# FIT_TCM_SN65LVDT100.net
KiCad netlist of a schematic drawn in Altium Designer
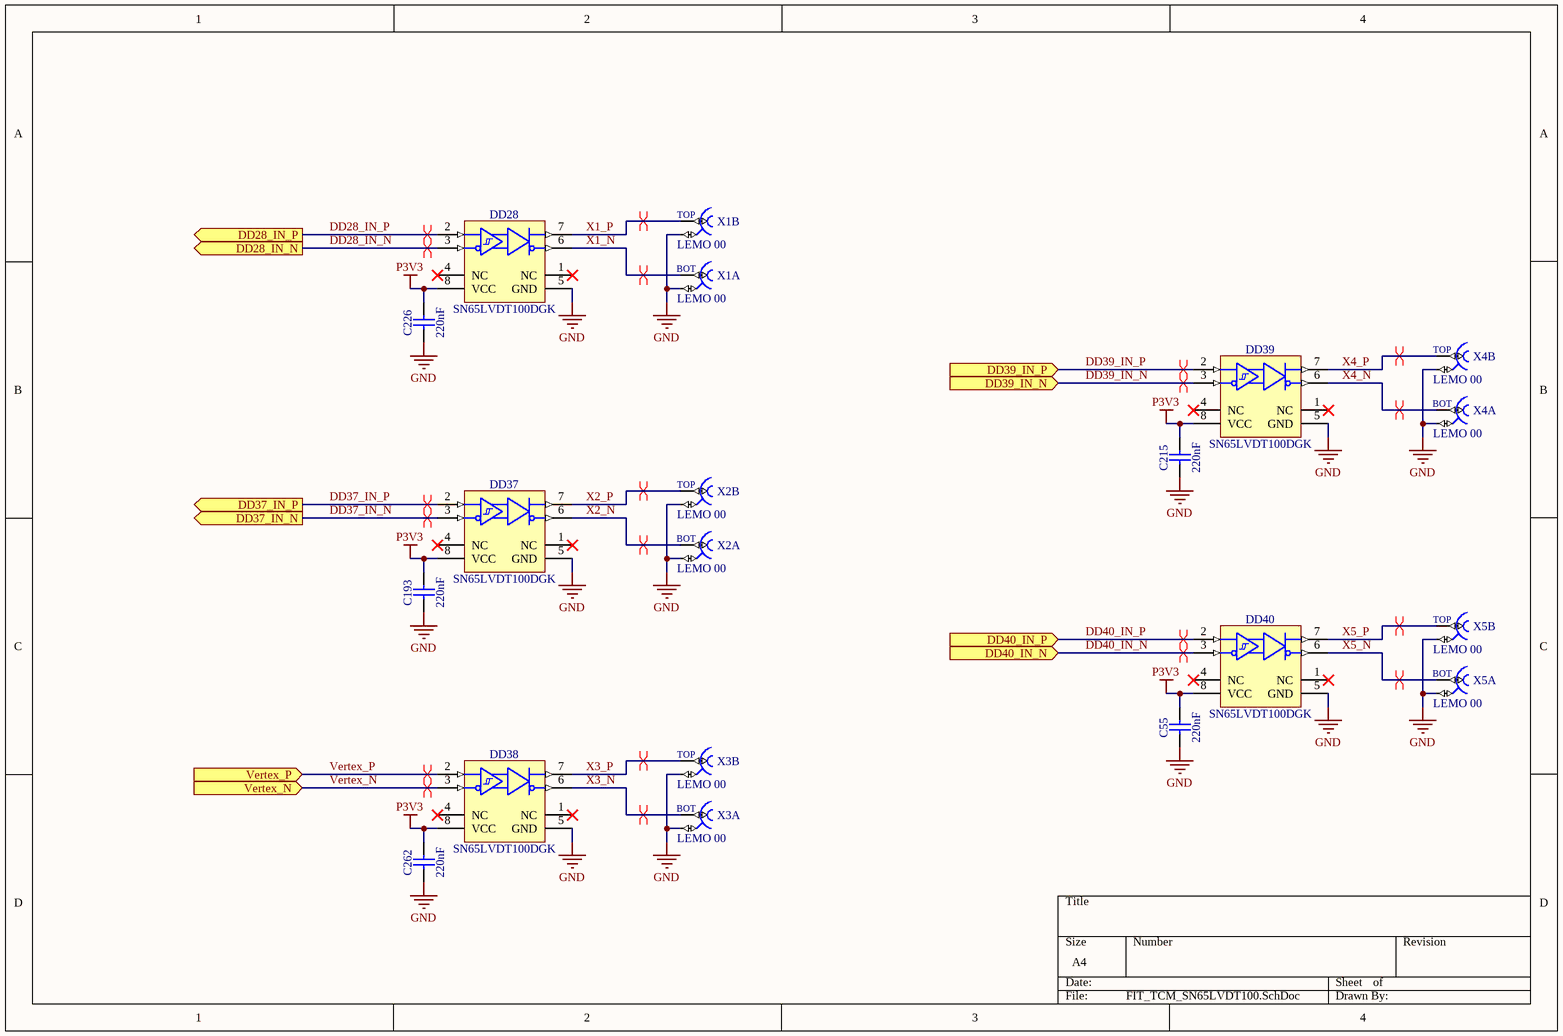
[diagram p0: FIT_TCM_SN65LVDT100.SchDoc]

(export (version "E")
  (design (tool "Eeschema 10.0.6"))
  (components
    (comp (ref "C55")
      (value "220nF")
      (footprint "CAPC2012X135N")
      (description "Non-polarised capacitor")
      (fields
        (field (name "PART NUMBER") "CC0805_220NF_50V_10%_X7R")
        (field (name "VOLTAGE") "50V")
        (field (name "AUTHOR") "CERN DEM JLC")
      )
      (libsource (lib "Capacitors") (part "Capacitor - non polarized"))
    )
    (comp (ref "C193")
      (value "220nF")
      (footprint "CAPC2012X135N")
      (description "Non-polarised capacitor")
      (fields
        (field (name "PART NUMBER") "CC0805_220NF_50V_10%_X7R")
        (field (name "VOLTAGE") "50V")
        (field (name "AUTHOR") "CERN DEM JLC")
      )
      (libsource (lib "Capacitors") (part "Capacitor - non polarized"))
    )
    (comp (ref "C215")
      (value "220nF")
      (footprint "CAPC2012X135N")
      (description "Non-polarised capacitor")
      (fields
        (field (name "PART NUMBER") "CC0805_220NF_50V_10%_X7R")
        (field (name "VOLTAGE") "50V")
        (field (name "AUTHOR") "CERN DEM JLC")
      )
      (libsource (lib "Capacitors") (part "Capacitor - non polarized"))
    )
    (comp (ref "C226")
      (value "220nF")
      (footprint "CAPC2012X135N")
      (description "Non-polarised capacitor")
      (fields
        (field (name "PART NUMBER") "CC0805_220NF_50V_10%_X7R")
        (field (name "VOLTAGE") "50V")
        (field (name "AUTHOR") "CERN DEM JLC")
      )
      (libsource (lib "Capacitors") (part "Capacitor - non polarized"))
    )
    (comp (ref "C262")
      (value "220nF")
      (footprint "CAPC2012X135N")
      (description "Non-polarised capacitor")
      (fields
        (field (name "PART NUMBER") "CC0805_220NF_50V_10%_X7R")
        (field (name "VOLTAGE") "50V")
        (field (name "AUTHOR") "CERN DEM JLC")
      )
      (libsource (lib "Capacitors") (part "Capacitor - non polarized"))
    )
    (comp (ref "DD28")
      (value "SN65LVDT100DGK")
      (footprint "SOP65P490X110-8N")
      (description "2Gbps LVDS/LVPECL/CML to LVDS Translator/Repeater")
      (fields (field (name "MANUFACTURER") "TEXAS INSTRUMENTS") (field (name "AUTHOR") "CERN DEM HF"))
      (libsource (lib "ICs And Semiconductors") (part "SN65LVDT100"))
    )
    (comp (ref "DD37")
      (value "SN65LVDT100DGK")
      (footprint "SOP65P490X110-8N")
      (description "2Gbps LVDS/LVPECL/CML to LVDS Translator/Repeater")
      (fields (field (name "MANUFACTURER") "TEXAS INSTRUMENTS") (field (name "AUTHOR") "CERN DEM HF"))
      (libsource (lib "ICs And Semiconductors") (part "SN65LVDT100"))
    )
    (comp (ref "DD38")
      (value "SN65LVDT100DGK")
      (footprint "SOP65P490X110-8N")
      (description "2Gbps LVDS/LVPECL/CML to LVDS Translator/Repeater")
      (fields (field (name "MANUFACTURER") "TEXAS INSTRUMENTS") (field (name "AUTHOR") "CERN DEM HF"))
      (libsource (lib "ICs And Semiconductors") (part "SN65LVDT100"))
    )
    (comp (ref "DD39")
      (value "SN65LVDT100DGK")
      (footprint "SOP65P490X110-8N")
      (description "2Gbps LVDS/LVPECL/CML to LVDS Translator/Repeater")
      (fields (field (name "MANUFACTURER") "TEXAS INSTRUMENTS") (field (name "AUTHOR") "CERN DEM HF"))
      (libsource (lib "ICs And Semiconductors") (part "SN65LVDT100"))
    )
    (comp (ref "DD40")
      (value "SN65LVDT100DGK")
      (footprint "SOP65P490X110-8N")
      (description "2Gbps LVDS/LVPECL/CML to LVDS Translator/Repeater")
      (fields (field (name "MANUFACTURER") "TEXAS INSTRUMENTS") (field (name "AUTHOR") "CERN DEM HF"))
      (libsource (lib "ICs And Semiconductors") (part "SN65LVDT100"))
    )
    (comp (ref "X1")
      (value "LEMO 00")
      (footprint "LEMO_EPY.00.250.NTN")
      (description "Dual Female Coax 1-2 Common Shield 3")
      (fields
        (field (name "PART NUMBER") "LEMO_EPY.00.250.NTN")
        (field (name "MANUFACTURER") "LEMO")
        (field (name "AUTHOR") "CERN DEM JMW")
      )
      (libsource (lib "Connectors") (part "LEMO_EPY.00.250.NTN"))
    )
    (comp (ref "X2")
      (value "LEMO 00")
      (footprint "LEMO_EPY.00.250.NTN")
      (description "Dual Female Coax 1-2 Common Shield 3")
      (fields
        (field (name "PART NUMBER") "LEMO_EPY.00.250.NTN")
        (field (name "MANUFACTURER") "LEMO")
        (field (name "AUTHOR") "CERN DEM JMW")
      )
      (libsource (lib "Connectors") (part "LEMO_EPY.00.250.NTN"))
    )
    (comp (ref "X3")
      (value "LEMO 00")
      (footprint "LEMO_EPY.00.250.NTN")
      (description "Dual Female Coax 1-2 Common Shield 3")
      (fields
        (field (name "PART NUMBER") "LEMO_EPY.00.250.NTN")
        (field (name "MANUFACTURER") "LEMO")
        (field (name "AUTHOR") "CERN DEM JMW")
      )
      (libsource (lib "Connectors") (part "LEMO_EPY.00.250.NTN"))
    )
    (comp (ref "X4")
      (value "LEMO 00")
      (footprint "LEMO_EPY.00.250.NTN")
      (description "Dual Female Coax 1-2 Common Shield 3")
      (fields
        (field (name "PART NUMBER") "LEMO_EPY.00.250.NTN")
        (field (name "MANUFACTURER") "LEMO")
        (field (name "AUTHOR") "CERN DEM JMW")
      )
      (libsource (lib "Connectors") (part "LEMO_EPY.00.250.NTN"))
    )
    (comp (ref "X5")
      (value "LEMO 00")
      (footprint "LEMO_EPY.00.250.NTN")
      (description "Dual Female Coax 1-2 Common Shield 3")
      (fields
        (field (name "PART NUMBER") "LEMO_EPY.00.250.NTN")
        (field (name "MANUFACTURER") "LEMO")
        (field (name "AUTHOR") "CERN DEM JMW")
      )
      (libsource (lib "Connectors") (part "LEMO_EPY.00.250.NTN"))
    )
  )
  (nets
    (net (code "1") (name "/DD28_IN_N") (class "Default")
      (node (ref "DD28") (pin "3") (pinfunction "B_3") (pintype "input"))
    )
    (net (code "2") (name "/DD28_IN_P") (class "Default")
      (node (ref "DD28") (pin "2") (pinfunction "A_2") (pintype "input"))
    )
    (net (code "3") (name "/DD37_IN_N") (class "Default")
      (node (ref "DD37") (pin "3") (pinfunction "B_3") (pintype "input"))
    )
    (net (code "4") (name "/DD37_IN_P") (class "Default")
      (node (ref "DD37") (pin "2") (pinfunction "A_2") (pintype "input"))
    )
    (net (code "5") (name "/DD39_IN_N") (class "Default")
      (node (ref "DD39") (pin "3") (pinfunction "B_3") (pintype "input"))
    )
    (net (code "6") (name "/DD39_IN_P") (class "Default")
      (node (ref "DD39") (pin "2") (pinfunction "A_2") (pintype "input"))
    )
    (net (code "7") (name "/DD40_IN_N") (class "Default")
      (node (ref "DD40") (pin "3") (pinfunction "B_3") (pintype "input"))
    )
    (net (code "8") (name "/DD40_IN_P") (class "Default")
      (node (ref "DD40") (pin "2") (pinfunction "A_2") (pintype "input"))
    )
    (net (code "9") (name "/Vertex_N") (class "Default")
      (node (ref "DD38") (pin "3") (pinfunction "B_3") (pintype "input"))
    )
    (net (code "10") (name "/Vertex_P") (class "Default")
      (node (ref "DD38") (pin "2") (pinfunction "A_2") (pintype "input"))
    )
    (net (code "11") (name "/X1_N") (class "Default")
      (node (ref "DD28") (pin "6") (pinfunction "Z_6") (pintype "output"))
      (node (ref "X1") (pin "1") (pinfunction "1_1") (pintype "bidirectional"))
    )
    (net (code "12") (name "/X1_P") (class "Default")
      (node (ref "DD28") (pin "7") (pinfunction "Y_7") (pintype "output"))
      (node (ref "X1") (pin "2") (pinfunction "2_2") (pintype "bidirectional"))
    )
    (net (code "13") (name "/X2_N") (class "Default")
      (node (ref "DD37") (pin "6") (pinfunction "Z_6") (pintype "output"))
      (node (ref "X2") (pin "1") (pinfunction "1_1") (pintype "bidirectional"))
    )
    (net (code "14") (name "/X2_P") (class "Default")
      (node (ref "DD37") (pin "7") (pinfunction "Y_7") (pintype "output"))
      (node (ref "X2") (pin "2") (pinfunction "2_2") (pintype "bidirectional"))
    )
    (net (code "15") (name "/X3_N") (class "Default")
      (node (ref "DD38") (pin "6") (pinfunction "Z_6") (pintype "output"))
      (node (ref "X3") (pin "1") (pinfunction "1_1") (pintype "bidirectional"))
    )
    (net (code "16") (name "/X3_P") (class "Default")
      (node (ref "DD38") (pin "7") (pinfunction "Y_7") (pintype "output"))
      (node (ref "X3") (pin "2") (pinfunction "2_2") (pintype "bidirectional"))
    )
    (net (code "17") (name "/X4_N") (class "Default")
      (node (ref "DD39") (pin "6") (pinfunction "Z_6") (pintype "output"))
      (node (ref "X4") (pin "1") (pinfunction "1_1") (pintype "bidirectional"))
    )
    (net (code "18") (name "/X4_P") (class "Default")
      (node (ref "DD39") (pin "7") (pinfunction "Y_7") (pintype "output"))
      (node (ref "X4") (pin "2") (pinfunction "2_2") (pintype "bidirectional"))
    )
    (net (code "19") (name "/X5_N") (class "Default")
      (node (ref "DD40") (pin "6") (pinfunction "Z_6") (pintype "output"))
      (node (ref "X5") (pin "1") (pinfunction "1_1") (pintype "bidirectional"))
    )
    (net (code "20") (name "/X5_P") (class "Default")
      (node (ref "DD40") (pin "7") (pinfunction "Y_7") (pintype "output"))
      (node (ref "X5") (pin "2") (pinfunction "2_2") (pintype "bidirectional"))
    )
    (net (code "21") (name "GND") (class "Default")
      (node (ref "C193") (pin "1") (pinfunction "1_1") (pintype "passive"))
      (node (ref "C215") (pin "1") (pinfunction "1_1") (pintype "passive"))
      (node (ref "C226") (pin "1") (pinfunction "1_1") (pintype "passive"))
      (node (ref "C262") (pin "1") (pinfunction "1_1") (pintype "passive"))
      (node (ref "C55") (pin "1") (pinfunction "1_1") (pintype "passive"))
      (node (ref "DD28") (pin "5") (pinfunction "GND_5") (pintype "power_in"))
      (node (ref "DD37") (pin "5") (pinfunction "GND_5") (pintype "power_in"))
      (node (ref "DD38") (pin "5") (pinfunction "GND_5") (pintype "power_in"))
      (node (ref "DD39") (pin "5") (pinfunction "GND_5") (pintype "power_in"))
      (node (ref "DD40") (pin "5") (pinfunction "GND_5") (pintype "power_in"))
      (node (ref "X1") (pin "3") (pinfunction "3_3") (pintype "bidirectional"))
      (node (ref "X2") (pin "3") (pinfunction "3_3") (pintype "bidirectional"))
      (node (ref "X3") (pin "3") (pinfunction "3_3") (pintype "bidirectional"))
      (node (ref "X4") (pin "3") (pinfunction "3_3") (pintype "bidirectional"))
      (node (ref "X5") (pin "3") (pinfunction "3_3") (pintype "bidirectional"))
    )
    (net (code "22") (name "P3V3") (class "Default")
      (node (ref "C193") (pin "2") (pinfunction "2_2") (pintype "passive"))
      (node (ref "C215") (pin "2") (pinfunction "2_2") (pintype "passive"))
      (node (ref "C226") (pin "2") (pinfunction "2_2") (pintype "passive"))
      (node (ref "C262") (pin "2") (pinfunction "2_2") (pintype "passive"))
      (node (ref "C55") (pin "2") (pinfunction "2_2") (pintype "passive"))
      (node (ref "DD28") (pin "8") (pinfunction "VCC_8") (pintype "power_in"))
      (node (ref "DD37") (pin "8") (pinfunction "VCC_8") (pintype "power_in"))
      (node (ref "DD38") (pin "8") (pinfunction "VCC_8") (pintype "power_in"))
      (node (ref "DD39") (pin "8") (pinfunction "VCC_8") (pintype "power_in"))
      (node (ref "DD40") (pin "8") (pinfunction "VCC_8") (pintype "power_in"))
    )
    (net (code "23") (name "unconnected-(DD28-NC-Pad1)") (class "Default")
      (node (ref "DD28") (pin "1") (pinfunction "NC_1") (pintype "passive+no_connect"))
    )
    (net (code "24") (name "unconnected-(DD28-NC-Pad4)") (class "Default")
      (node (ref "DD28") (pin "4") (pinfunction "NC_4") (pintype "passive+no_connect"))
    )
    (net (code "25") (name "unconnected-(DD37-NC-Pad1)") (class "Default")
      (node (ref "DD37") (pin "1") (pinfunction "NC_1") (pintype "passive+no_connect"))
    )
    (net (code "26") (name "unconnected-(DD37-NC-Pad4)") (class "Default")
      (node (ref "DD37") (pin "4") (pinfunction "NC_4") (pintype "passive+no_connect"))
    )
    (net (code "27") (name "unconnected-(DD38-NC-Pad1)") (class "Default")
      (node (ref "DD38") (pin "1") (pinfunction "NC_1") (pintype "passive+no_connect"))
    )
    (net (code "28") (name "unconnected-(DD38-NC-Pad4)") (class "Default")
      (node (ref "DD38") (pin "4") (pinfunction "NC_4") (pintype "passive+no_connect"))
    )
    (net (code "29") (name "unconnected-(DD39-NC-Pad1)") (class "Default")
      (node (ref "DD39") (pin "1") (pinfunction "NC_1") (pintype "passive+no_connect"))
    )
    (net (code "30") (name "unconnected-(DD39-NC-Pad4)") (class "Default")
      (node (ref "DD39") (pin "4") (pinfunction "NC_4") (pintype "passive+no_connect"))
    )
    (net (code "31") (name "unconnected-(DD40-NC-Pad1)") (class "Default")
      (node (ref "DD40") (pin "1") (pinfunction "NC_1") (pintype "passive+no_connect"))
    )
    (net (code "32") (name "unconnected-(DD40-NC-Pad4)") (class "Default")
      (node (ref "DD40") (pin "4") (pinfunction "NC_4") (pintype "passive+no_connect"))
    )
  )
)
